# PiHat-Extended.net
KiCad netlist of a schematic drawn in EAGLE
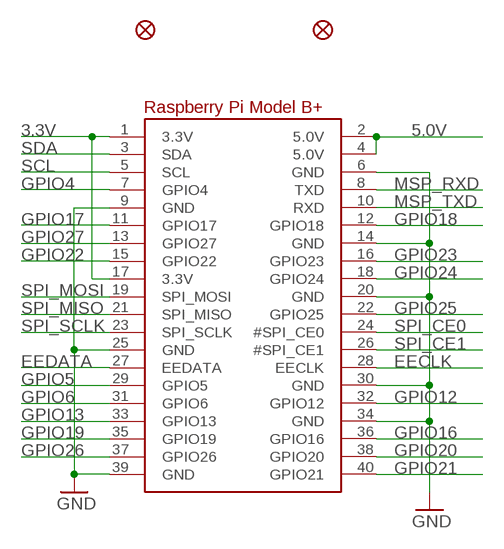
[diagram p0: schematic, sheet 1]
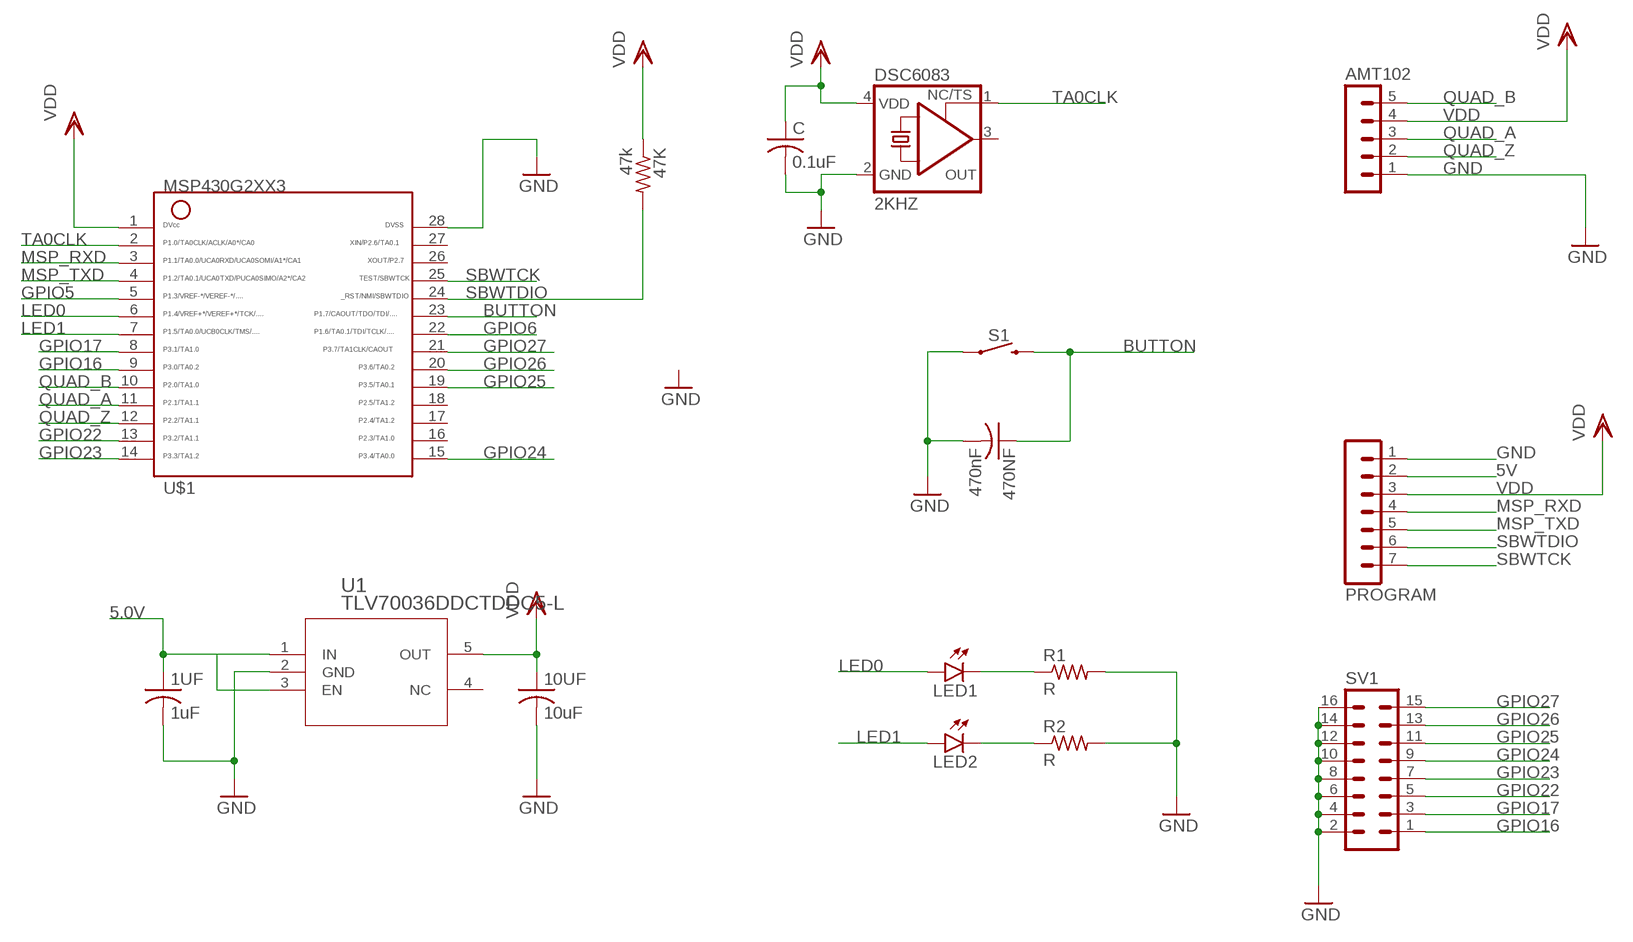
[diagram p1: schematic, sheet 2]
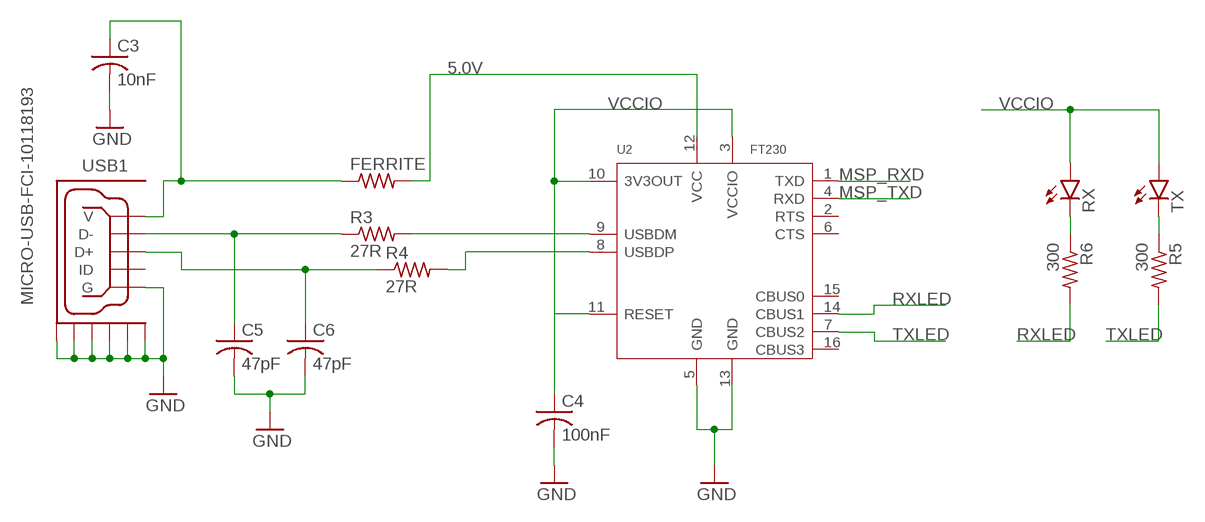
[diagram p2: schematic, sheet 3]
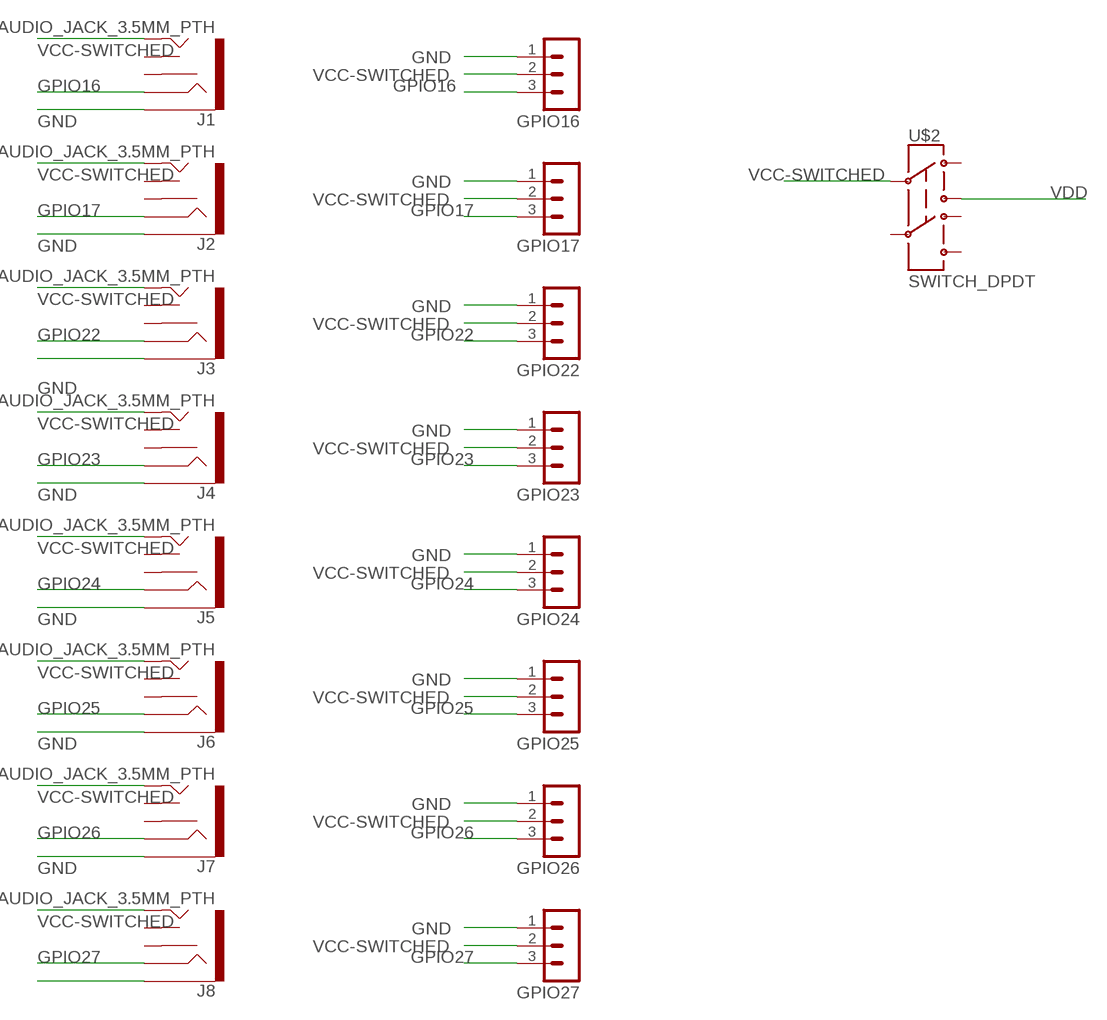
[diagram p3: schematic, sheet 4]

(export (version "E")
  (design (tool "Eeschema 10.0.6"))
  (components
    (comp (ref "GPIO16")
      (value "MA03-1")
      (footprint "eagle-import:MA03-1")
      (libsource (lib "eagle-import") (part "MA03-1"))
    )
    (comp (ref "GPIO17")
      (value "MA03-1")
      (footprint "eagle-import:MA03-1")
      (libsource (lib "eagle-import") (part "MA03-1"))
    )
    (comp (ref "GPIO22")
      (value "MA03-1")
      (footprint "eagle-import:MA03-1")
      (libsource (lib "eagle-import") (part "MA03-1"))
    )
    (comp (ref "GPIO23")
      (value "MA03-1")
      (footprint "eagle-import:MA03-1")
      (libsource (lib "eagle-import") (part "MA03-1"))
    )
    (comp (ref "GPIO24")
      (value "MA03-1")
      (footprint "eagle-import:MA03-1")
      (libsource (lib "eagle-import") (part "MA03-1"))
    )
    (comp (ref "GPIO25")
      (value "MA03-1")
      (footprint "eagle-import:MA03-1")
      (libsource (lib "eagle-import") (part "MA03-1"))
    )
    (comp (ref "GPIO26")
      (value "MA03-1")
      (footprint "eagle-import:MA03-1")
      (libsource (lib "eagle-import") (part "MA03-1"))
    )
    (comp (ref "GPIO27")
      (value "MA03-1")
      (footprint "eagle-import:MA03-1")
      (libsource (lib "eagle-import") (part "MA03-1"))
    )
    (comp (ref "J1")
      (value "AUDIO_JACK_3.5MM_PTH")
      (footprint "eagle-import:AUDIO-JACK")
      (libsource (lib "eagle-import") (part "AUDIO_JACK_3.5MM_PTH"))
    )
    (comp (ref "J2")
      (value "AUDIO_JACK_3.5MM_PTH")
      (footprint "eagle-import:AUDIO-JACK")
      (libsource (lib "eagle-import") (part "AUDIO_JACK_3.5MM_PTH"))
    )
    (comp (ref "J3")
      (value "AUDIO_JACK_3.5MM_PTH")
      (footprint "eagle-import:AUDIO-JACK")
      (libsource (lib "eagle-import") (part "AUDIO_JACK_3.5MM_PTH"))
    )
    (comp (ref "J4")
      (value "AUDIO_JACK_3.5MM_PTH")
      (footprint "eagle-import:AUDIO-JACK")
      (libsource (lib "eagle-import") (part "AUDIO_JACK_3.5MM_PTH"))
    )
    (comp (ref "J5")
      (value "AUDIO_JACK_3.5MM_PTH")
      (footprint "eagle-import:AUDIO-JACK")
      (libsource (lib "eagle-import") (part "AUDIO_JACK_3.5MM_PTH"))
    )
    (comp (ref "J6")
      (value "AUDIO_JACK_3.5MM_PTH")
      (footprint "eagle-import:AUDIO-JACK")
      (libsource (lib "eagle-import") (part "AUDIO_JACK_3.5MM_PTH"))
    )
    (comp (ref "J7")
      (value "AUDIO_JACK_3.5MM_PTH")
      (footprint "eagle-import:AUDIO-JACK")
      (libsource (lib "eagle-import") (part "AUDIO_JACK_3.5MM_PTH"))
    )
    (comp (ref "J8")
      (value "AUDIO_JACK_3.5MM_PTH")
      (footprint "eagle-import:AUDIO-JACK")
      (libsource (lib "eagle-import") (part "AUDIO_JACK_3.5MM_PTH"))
    )
    (comp (ref "U$2")
      (value "SWITCH_DPDT")
      (footprint "eagle-import:JS_DPDT_TH")
      (libsource (lib "eagle-import") (part "SWITCH_DPDT"))
    )
    (comp (ref "C3")
      (value "10nF")
      (footprint "eagle-import:C0603")
      (libsource (lib "eagle-import") (part "resistor_348_C-USC0603"))
    )
    (comp (ref "C4")
      (value "100nF")
      (footprint "eagle-import:C0603")
      (libsource (lib "eagle-import") (part "resistor_348_C-USC0603"))
    )
    (comp (ref "C5")
      (value "47pF")
      (footprint "eagle-import:C0603")
      (libsource (lib "eagle-import") (part "resistor_348_C-USC0603"))
    )
    (comp (ref "C6")
      (value "47pF")
      (footprint "eagle-import:C0603")
      (libsource (lib "eagle-import") (part "resistor_348_C-USC0603"))
    )
    (comp (ref "FERRITE")
      (value "R-US_R0805")
      (footprint "eagle-import:R0805")
      (libsource (lib "eagle-import") (part "R-US_R0805"))
    )
    (comp (ref "R3")
      (value "27R")
      (footprint "eagle-import:R0603")
      (libsource (lib "eagle-import") (part "resistor_348_R-US_R0603"))
    )
    (comp (ref "R4")
      (value "27R")
      (footprint "eagle-import:R0603")
      (libsource (lib "eagle-import") (part "resistor_348_R-US_R0603"))
    )
    (comp (ref "R5")
      (value "300")
      (footprint "eagle-import:R0603")
      (libsource (lib "eagle-import") (part "resistor_348_R-US_R0603"))
    )
    (comp (ref "R6")
      (value "300")
      (footprint "eagle-import:R0603")
      (libsource (lib "eagle-import") (part "resistor_348_R-US_R0603"))
    )
    (comp (ref "RX")
      (value "LEDCHIPLED_1206")
      (footprint "eagle-import:CHIPLED_1206")
      (libsource (lib "eagle-import") (part "LEDCHIPLED_1206"))
    )
    (comp (ref "TX")
      (value "LEDCHIPLED_1206")
      (footprint "eagle-import:CHIPLED_1206")
      (libsource (lib "eagle-import") (part "LEDCHIPLED_1206"))
    )
    (comp (ref "U2")
      (value "FT230")
      (footprint "eagle-import:SSOP16-0.635-5X4MM")
      (fields (field (name "MPN") "FT230XS-R"))
      (libsource (lib "eagle-import") (part "INTERFACE-FT230XS-R(SSOP16)"))
    )
    (comp (ref "USB1")
      (value "MICRO-USB-FCI-10118193")
      (footprint "eagle-import:FCI-10118193-0001LF")
      (libsource (lib "eagle-import") (part "MICRO-USB-FCI-10118193"))
    )
    (comp (ref "1UF")
      (value "1uF")
      (footprint "eagle-import:C0603")
      (libsource (lib "eagle-import") (part "C-USC0603"))
    )
    (comp (ref "10UF")
      (value "10uF")
      (footprint "eagle-import:C1206")
      (libsource (lib "eagle-import") (part "C-USC1206"))
    )
    (comp (ref "47K")
      (value "47k")
      (footprint "eagle-import:R0603")
      (libsource (lib "eagle-import") (part "R-US_R0603"))
    )
    (comp (ref "470NF")
      (value "470nF")
      (footprint "eagle-import:C0603")
      (libsource (lib "eagle-import") (part "C-USC0603"))
    )
    (comp (ref "AMT102")
      (value "MA05-1")
      (footprint "eagle-import:MA05-1")
      (libsource (lib "eagle-import") (part "MA05-1"))
    )
    (comp (ref "C")
      (value "0.1uF")
      (footprint "eagle-import:C0603")
      (libsource (lib "eagle-import") (part "C-USC0603"))
    )
    (comp (ref "DSC6083")
      (value "2KHZ")
      (footprint "eagle-import:3.2X2.5_KXO-V96")
      (libsource (lib "eagle-import") (part "KXO-PXO/XO-V96"))
    )
    (comp (ref "LED1")
      (value "LEDCHIPLED_1206")
      (footprint "eagle-import:CHIPLED_1206")
      (libsource (lib "eagle-import") (part "LEDCHIPLED_1206"))
    )
    (comp (ref "LED2")
      (value "LEDCHIPLED_1206")
      (footprint "eagle-import:CHIPLED_1206")
      (libsource (lib "eagle-import") (part "LEDCHIPLED_1206"))
    )
    (comp (ref "PROGRAM")
      (value "MA07-1")
      (footprint "eagle-import:MA07-1")
      (libsource (lib "eagle-import") (part "MA07-1"))
    )
    (comp (ref "R1")
      (value "R")
      (footprint "eagle-import:R0603")
      (libsource (lib "eagle-import") (part "R-US_R0603"))
    )
    (comp (ref "R2")
      (value "R")
      (footprint "eagle-import:R0603")
      (libsource (lib "eagle-import") (part "R-US_R0603"))
    )
    (comp (ref "S1")
      (value "MOMENTARY-SWITCH-SPST-PTH-6.0MM")
      (footprint "eagle-import:TACTILE_SWITCH_PTH_6.0MM")
      (libsource (lib "eagle-import") (part "MOMENTARY-SWITCH-SPST-PTH-6.0MM"))
    )
    (comp (ref "SV1")
      (value "MA08-2")
      (footprint "eagle-import:MA08-2")
      (libsource (lib "eagle-import") (part "MA08-2"))
    )
    (comp (ref "U$1")
      (value "MSP430")
      (footprint "eagle-import:PW28")
      (libsource (lib "eagle-import") (part "G2XX3---PW28"))
    )
    (comp (ref "U1")
      (value "TLV70036DDCTDDC5-L")
      (footprint "eagle-import:DDC5-L")
      (fields (field (name "MANUFACTURER_PART_NUMBER") "TLV70036DDCT"))
      (libsource (lib "eagle-import") (part "TLV70036DDCTDDC5-L"))
    )
    (comp (ref "FID2")
      (value "MICROBUILDER_FIDUCIAL\"\"")
      (footprint "eagle-import:MICROBUILDER_FIDUCIAL_1MM")
      (libsource (lib "eagle-import") (part "MICROBUILDER_FIDUCIAL{dblquote}{dblquote}"))
    )
    (comp (ref "FID3")
      (value "MICROBUILDER_FIDUCIAL\"\"")
      (footprint "eagle-import:MICROBUILDER_FIDUCIAL_1MM")
      (libsource (lib "eagle-import") (part "MICROBUILDER_FIDUCIAL{dblquote}{dblquote}"))
    )
    (comp (ref "RPI1")
      (value "MICROBUILDER_RASPBERRYPI_BPLUS_HATNOSLOTS")
      (footprint "eagle-import:MICROBUILDER_PI_HAT_NOSLOTS")
      (libsource (lib "eagle-import") (part "MICROBUILDER_RASPBERRYPI_BPLUS_HATNOSLOTS"))
    )
  )
  (nets
    (net (code "1") (name "3.3V") (class "Default")
      (node (ref "RPI1") (pin "1") (pinfunction "3.3V_1") (pintype "power_in"))
      (node (ref "RPI1") (pin "17") (pinfunction "3.3V_17") (pintype "power_in"))
    )
    (net (code "2") (name "5.0V") (class "Default")
      (node (ref "1UF") (pin "1") (pinfunction "1_1") (pintype "passive"))
      (node (ref "FERRITE") (pin "2") (pinfunction "2_2") (pintype "passive"))
      (node (ref "RPI1") (pin "2") (pinfunction "5.0V_2") (pintype "power_in"))
      (node (ref "RPI1") (pin "4") (pinfunction "5.0V_4") (pintype "power_in"))
      (node (ref "U1") (pin "1") (pinfunction "IN_1") (pintype "input"))
      (node (ref "U1") (pin "3") (pinfunction "EN_3") (pintype "passive"))
      (node (ref "U2") (pin "12") (pinfunction "VCC_12") (pintype "bidirectional"))
    )
    (net (code "3") (name "5V") (class "Default")
      (node (ref "PROGRAM") (pin "2") (pinfunction "2_2") (pintype "passive"))
    )
    (net (code "4") (name "BUTTON") (class "Default")
      (node (ref "470NF") (pin "1") (pinfunction "1_1") (pintype "passive"))
      (node (ref "S1") (pin "3") (pinfunction "2_3") (pintype "passive"))
      (node (ref "U$1") (pin "23") (pinfunction "23_23") (pintype "bidirectional"))
    )
    (net (code "5") (name "EECLK") (class "Default")
      (node (ref "RPI1") (pin "28") (pinfunction "EECLK_28") (pintype "power_in"))
    )
    (net (code "6") (name "EEDATA") (class "Default")
      (node (ref "RPI1") (pin "27") (pinfunction "EEDATA_27") (pintype "bidirectional"))
    )
    (net (code "7") (name "GND") (class "Default")
      (node (ref "10UF") (pin "2") (pinfunction "2_2") (pintype "passive"))
      (node (ref "1UF") (pin "2") (pinfunction "2_2") (pintype "passive"))
      (node (ref "470NF") (pin "2") (pinfunction "2_2") (pintype "passive"))
      (node (ref "AMT102") (pin "1") (pinfunction "1_1") (pintype "passive"))
      (node (ref "C") (pin "2") (pinfunction "2_2") (pintype "passive"))
      (node (ref "C3") (pin "2") (pinfunction "2_2") (pintype "passive"))
      (node (ref "C4") (pin "2") (pinfunction "2_2") (pintype "passive"))
      (node (ref "C5") (pin "2") (pinfunction "2_2") (pintype "passive"))
      (node (ref "C6") (pin "2") (pinfunction "2_2") (pintype "passive"))
      (node (ref "DSC6083") (pin "2") (pinfunction "GND_2") (pintype "power_in"))
      (node (ref "GPIO16") (pin "1") (pinfunction "1_1") (pintype "passive"))
      (node (ref "GPIO17") (pin "1") (pinfunction "1_1") (pintype "passive"))
      (node (ref "GPIO22") (pin "1") (pinfunction "1_1") (pintype "passive"))
      (node (ref "GPIO23") (pin "1") (pinfunction "1_1") (pintype "passive"))
      (node (ref "GPIO24") (pin "1") (pinfunction "1_1") (pintype "passive"))
      (node (ref "GPIO25") (pin "1") (pinfunction "1_1") (pintype "passive"))
      (node (ref "GPIO26") (pin "1") (pinfunction "1_1") (pintype "passive"))
      (node (ref "GPIO27") (pin "1") (pinfunction "1_1") (pintype "passive"))
      (node (ref "J1") (pin "SLEEVE") (pinfunction "SLEEVE_SLEEVE") (pintype "bidirectional"))
      (node (ref "J2") (pin "SLEEVE") (pinfunction "SLEEVE_SLEEVE") (pintype "bidirectional"))
      (node (ref "J3") (pin "SLEEVE") (pinfunction "SLEEVE_SLEEVE") (pintype "bidirectional"))
      (node (ref "J4") (pin "SLEEVE") (pinfunction "SLEEVE_SLEEVE") (pintype "bidirectional"))
      (node (ref "J5") (pin "SLEEVE") (pinfunction "SLEEVE_SLEEVE") (pintype "bidirectional"))
      (node (ref "J6") (pin "SLEEVE") (pinfunction "SLEEVE_SLEEVE") (pintype "bidirectional"))
      (node (ref "J7") (pin "SLEEVE") (pinfunction "SLEEVE_SLEEVE") (pintype "bidirectional"))
      (node (ref "J8") (pin "SLEEVE") (pinfunction "SLEEVE_SLEEVE") (pintype "bidirectional"))
      (node (ref "PROGRAM") (pin "1") (pinfunction "1_1") (pintype "passive"))
      (node (ref "R1") (pin "2") (pinfunction "2_2") (pintype "passive"))
      (node (ref "R2") (pin "2") (pinfunction "2_2") (pintype "passive"))
      (node (ref "RPI1") (pin "14") (pinfunction "GND_14") (pintype "power_in"))
      (node (ref "RPI1") (pin "20") (pinfunction "GND_20") (pintype "power_in"))
      (node (ref "RPI1") (pin "25") (pinfunction "GND_25") (pintype "power_in"))
      (node (ref "RPI1") (pin "30") (pinfunction "GND_30") (pintype "bidirectional"))
      (node (ref "RPI1") (pin "34") (pinfunction "GND_34") (pintype "bidirectional"))
      (node (ref "RPI1") (pin "39") (pinfunction "GND_39") (pintype "power_in"))
      (node (ref "RPI1") (pin "6") (pinfunction "GND_6") (pintype "power_in"))
      (node (ref "RPI1") (pin "9") (pinfunction "GND_9") (pintype "power_in"))
      (node (ref "S1") (pin "1") (pinfunction "1_1") (pintype "passive"))
      (node (ref "SV1") (pin "10") (pinfunction "10_10") (pintype "passive"))
      (node (ref "SV1") (pin "12") (pinfunction "12_12") (pintype "passive"))
      (node (ref "SV1") (pin "14") (pinfunction "14_14") (pintype "passive"))
      (node (ref "SV1") (pin "16") (pinfunction "16_16") (pintype "passive"))
      (node (ref "SV1") (pin "2") (pinfunction "2_2") (pintype "passive"))
      (node (ref "SV1") (pin "4") (pinfunction "4_4") (pintype "passive"))
      (node (ref "SV1") (pin "6") (pinfunction "6_6") (pintype "passive"))
      (node (ref "SV1") (pin "8") (pinfunction "8_8") (pintype "passive"))
      (node (ref "U$1") (pin "28") (pinfunction "28_28") (pintype "bidirectional"))
      (node (ref "U1") (pin "2") (pinfunction "GND_2") (pintype "power_in"))
      (node (ref "U2") (pin "13") (pinfunction "GND_13") (pintype "bidirectional"))
      (node (ref "U2") (pin "5") (pinfunction "GND_5") (pintype "bidirectional"))
      (node (ref "USB1") (pin "5") (pinfunction "G_5") (pintype "input"))
      (node (ref "USB1") (pin "G1") (pinfunction "GND1_G1") (pintype "power_in"))
      (node (ref "USB1") (pin "G2") (pinfunction "GND2_G2") (pintype "power_in"))
      (node (ref "USB1") (pin "G3") (pinfunction "GND3_G3") (pintype "power_in"))
      (node (ref "USB1") (pin "G4") (pinfunction "GND4_G4") (pintype "power_in"))
      (node (ref "USB1") (pin "G5") (pinfunction "GND5_G5") (pintype "power_in"))
      (node (ref "USB1") (pin "G6") (pinfunction "GND6_G6") (pintype "power_in"))
    )
    (net (code "8") (name "GPIO4") (class "Default")
      (node (ref "RPI1") (pin "7") (pinfunction "GPIO4_7") (pintype "bidirectional"))
    )
    (net (code "9") (name "GPIO5") (class "Default")
      (node (ref "RPI1") (pin "29") (pinfunction "GPIO5_29") (pintype "bidirectional"))
      (node (ref "U$1") (pin "5") (pinfunction "5_5") (pintype "bidirectional"))
    )
    (net (code "10") (name "GPIO6") (class "Default")
      (node (ref "RPI1") (pin "31") (pinfunction "GPIO6_31") (pintype "power_in"))
      (node (ref "U$1") (pin "22") (pinfunction "22_22") (pintype "bidirectional"))
    )
    (net (code "11") (name "GPIO12") (class "Default")
      (node (ref "RPI1") (pin "32") (pinfunction "GPIO12_32") (pintype "bidirectional"))
    )
    (net (code "12") (name "GPIO13") (class "Default")
      (node (ref "RPI1") (pin "33") (pinfunction "GPIO13_33") (pintype "bidirectional"))
    )
    (net (code "13") (name "GPIO16") (class "Default")
      (node (ref "GPIO16") (pin "3") (pinfunction "3_3") (pintype "passive"))
      (node (ref "J1") (pin "RING") (pinfunction "RING_RING") (pintype "bidirectional"))
      (node (ref "RPI1") (pin "36") (pinfunction "GPIO16_36") (pintype "power_in"))
      (node (ref "SV1") (pin "1") (pinfunction "1_1") (pintype "passive"))
      (node (ref "U$1") (pin "9") (pinfunction "9_9") (pintype "bidirectional"))
    )
    (net (code "14") (name "GPIO17") (class "Default")
      (node (ref "GPIO17") (pin "3") (pinfunction "3_3") (pintype "passive"))
      (node (ref "J2") (pin "RING") (pinfunction "RING_RING") (pintype "bidirectional"))
      (node (ref "RPI1") (pin "11") (pinfunction "GPIO17_11") (pintype "bidirectional"))
      (node (ref "SV1") (pin "3") (pinfunction "3_3") (pintype "passive"))
      (node (ref "U$1") (pin "8") (pinfunction "8_8") (pintype "bidirectional"))
    )
    (net (code "15") (name "GPIO18") (class "Default")
      (node (ref "RPI1") (pin "12") (pinfunction "GPIO18_12") (pintype "bidirectional"))
    )
    (net (code "16") (name "GPIO19") (class "Default")
      (node (ref "RPI1") (pin "35") (pinfunction "GPIO19_35") (pintype "bidirectional"))
    )
    (net (code "17") (name "GPIO20") (class "Default")
      (node (ref "RPI1") (pin "38") (pinfunction "GPIO20_38") (pintype "bidirectional"))
    )
    (net (code "18") (name "GPIO21") (class "Default")
      (node (ref "RPI1") (pin "40") (pinfunction "GPIO21_40") (pintype "bidirectional"))
    )
    (net (code "19") (name "GPIO22") (class "Default")
      (node (ref "GPIO22") (pin "3") (pinfunction "3_3") (pintype "passive"))
      (node (ref "J3") (pin "RING") (pinfunction "RING_RING") (pintype "bidirectional"))
      (node (ref "RPI1") (pin "15") (pinfunction "GPIO22_15") (pintype "bidirectional"))
      (node (ref "SV1") (pin "5") (pinfunction "5_5") (pintype "passive"))
      (node (ref "U$1") (pin "13") (pinfunction "13_13") (pintype "bidirectional"))
    )
    (net (code "20") (name "GPIO23") (class "Default")
      (node (ref "GPIO23") (pin "3") (pinfunction "3_3") (pintype "passive"))
      (node (ref "J4") (pin "RING") (pinfunction "RING_RING") (pintype "bidirectional"))
      (node (ref "RPI1") (pin "16") (pinfunction "GPIO23_16") (pintype "bidirectional"))
      (node (ref "SV1") (pin "7") (pinfunction "7_7") (pintype "passive"))
      (node (ref "U$1") (pin "14") (pinfunction "14_14") (pintype "bidirectional"))
    )
    (net (code "21") (name "GPIO24") (class "Default")
      (node (ref "GPIO24") (pin "3") (pinfunction "3_3") (pintype "passive"))
      (node (ref "J5") (pin "RING") (pinfunction "RING_RING") (pintype "bidirectional"))
      (node (ref "RPI1") (pin "18") (pinfunction "GPIO24_18") (pintype "bidirectional"))
      (node (ref "SV1") (pin "9") (pinfunction "9_9") (pintype "passive"))
      (node (ref "U$1") (pin "15") (pinfunction "15_15") (pintype "bidirectional"))
    )
    (net (code "22") (name "GPIO25") (class "Default")
      (node (ref "GPIO25") (pin "3") (pinfunction "3_3") (pintype "passive"))
      (node (ref "J6") (pin "RING") (pinfunction "RING_RING") (pintype "bidirectional"))
      (node (ref "RPI1") (pin "22") (pinfunction "GPIO25_22") (pintype "bidirectional"))
      (node (ref "SV1") (pin "11") (pinfunction "11_11") (pintype "passive"))
      (node (ref "U$1") (pin "19") (pinfunction "19_19") (pintype "bidirectional"))
    )
    (net (code "23") (name "GPIO26") (class "Default")
      (node (ref "GPIO26") (pin "3") (pinfunction "3_3") (pintype "passive"))
      (node (ref "J7") (pin "RING") (pinfunction "RING_RING") (pintype "bidirectional"))
      (node (ref "RPI1") (pin "37") (pinfunction "GPIO26_37") (pintype "bidirectional"))
      (node (ref "SV1") (pin "13") (pinfunction "13_13") (pintype "passive"))
      (node (ref "U$1") (pin "20") (pinfunction "20_20") (pintype "bidirectional"))
    )
    (net (code "24") (name "GPIO27") (class "Default")
      (node (ref "GPIO27") (pin "3") (pinfunction "3_3") (pintype "passive"))
      (node (ref "J8") (pin "RING") (pinfunction "RING_RING") (pintype "bidirectional"))
      (node (ref "RPI1") (pin "13") (pinfunction "GPIO27_13") (pintype "bidirectional"))
      (node (ref "SV1") (pin "15") (pinfunction "15_15") (pintype "passive"))
      (node (ref "U$1") (pin "21") (pinfunction "21_21") (pintype "bidirectional"))
    )
    (net (code "25") (name "LED0") (class "Default")
      (node (ref "LED1") (pin "A") (pinfunction "A_A") (pintype "passive"))
      (node (ref "U$1") (pin "6") (pinfunction "6_6") (pintype "bidirectional"))
    )
    (net (code "26") (name "LED1") (class "Default")
      (node (ref "LED2") (pin "A") (pinfunction "A_A") (pintype "passive"))
      (node (ref "U$1") (pin "7") (pinfunction "7_7") (pintype "bidirectional"))
    )
    (net (code "27") (name "MSP_RXD") (class "Default")
      (node (ref "PROGRAM") (pin "4") (pinfunction "4_4") (pintype "passive"))
      (node (ref "RPI1") (pin "8") (pinfunction "TXD_8") (pintype "output"))
      (node (ref "U$1") (pin "3") (pinfunction "3_3") (pintype "bidirectional"))
      (node (ref "U2") (pin "1") (pinfunction "TXD_1") (pintype "bidirectional"))
    )
    (net (code "28") (name "MSP_TXD") (class "Default")
      (node (ref "PROGRAM") (pin "5") (pinfunction "5_5") (pintype "passive"))
      (node (ref "RPI1") (pin "10") (pinfunction "RXD_10") (pintype "bidirectional"))
      (node (ref "U$1") (pin "4") (pinfunction "4_4") (pintype "bidirectional"))
      (node (ref "U2") (pin "4") (pinfunction "RXD_4") (pintype "bidirectional"))
    )
    (net (code "29") (name "Net-(LED1-PadC)") (class "Default")
      (node (ref "LED1") (pin "C") (pinfunction "C_C") (pintype "passive"))
      (node (ref "R1") (pin "1") (pinfunction "1_1") (pintype "passive"))
    )
    (net (code "30") (name "Net-(LED2-PadC)") (class "Default")
      (node (ref "LED2") (pin "C") (pinfunction "C_C") (pintype "passive"))
      (node (ref "R2") (pin "1") (pinfunction "1_1") (pintype "passive"))
    )
    (net (code "31") (name "Net-(R5-Pad1)") (class "Default")
      (node (ref "R5") (pin "1") (pinfunction "1_1") (pintype "passive"))
      (node (ref "TX") (pin "C") (pinfunction "C_C") (pintype "passive"))
    )
    (net (code "32") (name "Net-(R6-Pad1)") (class "Default")
      (node (ref "R6") (pin "1") (pinfunction "1_1") (pintype "passive"))
      (node (ref "RX") (pin "C") (pinfunction "C_C") (pintype "passive"))
    )
    (net (code "33") (name "Net-(U2-USBDM)") (class "Default")
      (node (ref "R3") (pin "2") (pinfunction "2_2") (pintype "passive"))
      (node (ref "U2") (pin "9") (pinfunction "USBDM_9") (pintype "bidirectional"))
    )
    (net (code "34") (name "Net-(U2-USBDP)") (class "Default")
      (node (ref "R4") (pin "2") (pinfunction "2_2") (pintype "passive"))
      (node (ref "U2") (pin "8") (pinfunction "USBDP_8") (pintype "bidirectional"))
    )
    (net (code "35") (name "Net-(USB1-D+)") (class "Default")
      (node (ref "C6") (pin "1") (pinfunction "1_1") (pintype "passive"))
      (node (ref "R4") (pin "1") (pinfunction "1_1") (pintype "passive"))
      (node (ref "USB1") (pin "3") (pinfunction "D+_3") (pintype "input"))
    )
    (net (code "36") (name "Net-(USB1-D-)") (class "Default")
      (node (ref "C5") (pin "1") (pinfunction "1_1") (pintype "passive"))
      (node (ref "R3") (pin "1") (pinfunction "1_1") (pintype "passive"))
      (node (ref "USB1") (pin "2") (pinfunction "D-_2") (pintype "input"))
    )
    (net (code "37") (name "Net-(USB1-V)") (class "Default")
      (node (ref "C3") (pin "1") (pinfunction "1_1") (pintype "passive"))
      (node (ref "FERRITE") (pin "1") (pinfunction "1_1") (pintype "passive"))
      (node (ref "USB1") (pin "1") (pinfunction "V_1") (pintype "input"))
    )
    (net (code "38") (name "QUAD_A") (class "Default")
      (node (ref "AMT102") (pin "3") (pinfunction "3_3") (pintype "passive"))
      (node (ref "U$1") (pin "11") (pinfunction "11_11") (pintype "bidirectional"))
    )
    (net (code "39") (name "QUAD_B") (class "Default")
      (node (ref "AMT102") (pin "5") (pinfunction "5_5") (pintype "passive"))
      (node (ref "U$1") (pin "10") (pinfunction "10_10") (pintype "bidirectional"))
    )
    (net (code "40") (name "QUAD_Z") (class "Default")
      (node (ref "AMT102") (pin "2") (pinfunction "2_2") (pintype "passive"))
      (node (ref "U$1") (pin "12") (pinfunction "12_12") (pintype "bidirectional"))
    )
    (net (code "41") (name "RXLED") (class "Default")
      (node (ref "R6") (pin "2") (pinfunction "2_2") (pintype "passive"))
      (node (ref "U2") (pin "14") (pinfunction "CBUS1_14") (pintype "bidirectional"))
    )
    (net (code "42") (name "SBWTCK") (class "Default")
      (node (ref "PROGRAM") (pin "7") (pinfunction "7_7") (pintype "passive"))
      (node (ref "U$1") (pin "25") (pinfunction "25_25") (pintype "bidirectional"))
    )
    (net (code "43") (name "SBWTDIO") (class "Default")
      (node (ref "47K") (pin "2") (pinfunction "2_2") (pintype "passive"))
      (node (ref "PROGRAM") (pin "6") (pinfunction "6_6") (pintype "passive"))
      (node (ref "U$1") (pin "24") (pinfunction "24_24") (pintype "bidirectional"))
    )
    (net (code "44") (name "SCL") (class "Default")
      (node (ref "RPI1") (pin "5") (pinfunction "SCL_5") (pintype "bidirectional"))
    )
    (net (code "45") (name "SDA") (class "Default")
      (node (ref "RPI1") (pin "3") (pinfunction "SDA_3") (pintype "bidirectional"))
    )
    (net (code "46") (name "SPI_CE0") (class "Default")
      (node (ref "RPI1") (pin "24") (pinfunction "#SPI_CE0_24") (pintype "bidirectional"))
    )
    (net (code "47") (name "SPI_CE1") (class "Default")
      (node (ref "RPI1") (pin "26") (pinfunction "#SPI_CE1_26") (pintype "bidirectional"))
    )
    (net (code "48") (name "SPI_MISO") (class "Default")
      (node (ref "RPI1") (pin "21") (pinfunction "SPI_MISO_21") (pintype "bidirectional"))
    )
    (net (code "49") (name "SPI_MOSI") (class "Default")
      (node (ref "RPI1") (pin "19") (pinfunction "SPI_MOSI_19") (pintype "bidirectional"))
    )
    (net (code "50") (name "SPI_SCLK") (class "Default")
      (node (ref "RPI1") (pin "23") (pinfunction "SPI_SCLK_23") (pintype "bidirectional"))
    )
    (net (code "51") (name "TA0CLK") (class "Default")
      (node (ref "DSC6083") (pin "1") (pinfunction "TS_1") (pintype "passive"))
      (node (ref "U$1") (pin "2") (pinfunction "2_2") (pintype "bidirectional"))
    )
    (net (code "52") (name "TXLED") (class "Default")
      (node (ref "R5") (pin "2") (pinfunction "2_2") (pintype "passive"))
      (node (ref "U2") (pin "7") (pinfunction "CBUS2_7") (pintype "bidirectional"))
    )
    (net (code "53") (name "VCC-SWITCHED") (class "Default")
      (node (ref "GPIO16") (pin "2") (pinfunction "2_2") (pintype "passive"))
      (node (ref "GPIO17") (pin "2") (pinfunction "2_2") (pintype "passive"))
      (node (ref "GPIO22") (pin "2") (pinfunction "2_2") (pintype "passive"))
      (node (ref "GPIO23") (pin "2") (pinfunction "2_2") (pintype "passive"))
      (node (ref "GPIO24") (pin "2") (pinfunction "2_2") (pintype "passive"))
      (node (ref "GPIO25") (pin "2") (pinfunction "2_2") (pintype "passive"))
      (node (ref "GPIO26") (pin "2") (pinfunction "2_2") (pintype "passive"))
      (node (ref "GPIO27") (pin "2") (pinfunction "2_2") (pintype "passive"))
      (node (ref "J1") (pin "TIP") (pinfunction "TIP_TIP") (pintype "bidirectional"))
      (node (ref "J2") (pin "TIP") (pinfunction "TIP_TIP") (pintype "bidirectional"))
      (node (ref "J3") (pin "TIP") (pinfunction "TIP_TIP") (pintype "bidirectional"))
      (node (ref "J4") (pin "TIP") (pinfunction "TIP_TIP") (pintype "bidirectional"))
      (node (ref "J5") (pin "TIP") (pinfunction "TIP_TIP") (pintype "bidirectional"))
      (node (ref "J6") (pin "TIP") (pinfunction "TIP_TIP") (pintype "bidirectional"))
      (node (ref "J7") (pin "TIP") (pinfunction "TIP_TIP") (pintype "bidirectional"))
      (node (ref "J8") (pin "TIP") (pinfunction "TIP_TIP") (pintype "bidirectional"))
      (node (ref "U$2") (pin "2") (pinfunction "2_2") (pintype "bidirectional"))
    )
    (net (code "54") (name "VCCIO") (class "Default")
      (node (ref "C4") (pin "1") (pinfunction "1_1") (pintype "passive"))
      (node (ref "RX") (pin "A") (pinfunction "A_A") (pintype "passive"))
      (node (ref "TX") (pin "A") (pinfunction "A_A") (pintype "passive"))
      (node (ref "U2") (pin "10") (pinfunction "3V3OUT_10") (pintype "bidirectional"))
      (node (ref "U2") (pin "11") (pinfunction "RESET_11") (pintype "bidirectional"))
      (node (ref "U2") (pin "3") (pinfunction "VCCIO_3") (pintype "bidirectional"))
    )
    (net (code "55") (name "VDD") (class "Default")
      (node (ref "10UF") (pin "1") (pinfunction "1_1") (pintype "passive"))
      (node (ref "47K") (pin "1") (pinfunction "1_1") (pintype "passive"))
      (node (ref "AMT102") (pin "4") (pinfunction "4_4") (pintype "passive"))
      (node (ref "C") (pin "1") (pinfunction "1_1") (pintype "passive"))
      (node (ref "DSC6083") (pin "4") (pinfunction "VDD_4") (pintype "power_in"))
      (node (ref "PROGRAM") (pin "3") (pinfunction "3_3") (pintype "passive"))
      (node (ref "U$1") (pin "1") (pinfunction "1_1") (pintype "bidirectional"))
      (node (ref "U$2") (pin "3") (pinfunction "3_3") (pintype "bidirectional"))
      (node (ref "U1") (pin "5") (pinfunction "OUT_5") (pintype "output"))
    )
    (net (code "56") (name "unconnected-(DSC6083-OUT-Pad3)") (class "Default")
      (node (ref "DSC6083") (pin "3") (pinfunction "OUT_3") (pintype "output"))
    )
    (net (code "57") (name "unconnected-(J1-PadRSH)") (class "Default")
      (node (ref "J1") (pin "RSH") (pinfunction "RSH_RSH") (pintype "bidirectional"))
    )
    (net (code "58") (name "unconnected-(J1-PadTSH)") (class "Default")
      (node (ref "J1") (pin "TSH") (pinfunction "TSH_TSH") (pintype "bidirectional"))
    )
    (net (code "59") (name "unconnected-(J2-PadRSH)") (class "Default")
      (node (ref "J2") (pin "RSH") (pinfunction "RSH_RSH") (pintype "bidirectional"))
    )
    (net (code "60") (name "unconnected-(J2-PadTSH)") (class "Default")
      (node (ref "J2") (pin "TSH") (pinfunction "TSH_TSH") (pintype "bidirectional"))
    )
    (net (code "61") (name "unconnected-(J3-PadRSH)") (class "Default")
      (node (ref "J3") (pin "RSH") (pinfunction "RSH_RSH") (pintype "bidirectional"))
    )
    (net (code "62") (name "unconnected-(J3-PadTSH)") (class "Default")
      (node (ref "J3") (pin "TSH") (pinfunction "TSH_TSH") (pintype "bidirectional"))
    )
    (net (code "63") (name "unconnected-(J4-PadRSH)") (class "Default")
      (node (ref "J4") (pin "RSH") (pinfunction "RSH_RSH") (pintype "bidirectional"))
    )
    (net (code "64") (name "unconnected-(J4-PadTSH)") (class "Default")
      (node (ref "J4") (pin "TSH") (pinfunction "TSH_TSH") (pintype "bidirectional"))
    )
    (net (code "65") (name "unconnected-(J5-PadRSH)") (class "Default")
      (node (ref "J5") (pin "RSH") (pinfunction "RSH_RSH") (pintype "bidirectional"))
    )
    (net (code "66") (name "unconnected-(J5-PadTSH)") (class "Default")
      (node (ref "J5") (pin "TSH") (pinfunction "TSH_TSH") (pintype "bidirectional"))
    )
    (net (code "67") (name "unconnected-(J6-PadRSH)") (class "Default")
      (node (ref "J6") (pin "RSH") (pinfunction "RSH_RSH") (pintype "bidirectional"))
    )
    (net (code "68") (name "unconnected-(J6-PadTSH)") (class "Default")
      (node (ref "J6") (pin "TSH") (pinfunction "TSH_TSH") (pintype "bidirectional"))
    )
    (net (code "69") (name "unconnected-(J7-PadRSH)") (class "Default")
      (node (ref "J7") (pin "RSH") (pinfunction "RSH_RSH") (pintype "bidirectional"))
    )
    (net (code "70") (name "unconnected-(J7-PadTSH)") (class "Default")
      (node (ref "J7") (pin "TSH") (pinfunction "TSH_TSH") (pintype "bidirectional"))
    )
    (net (code "71") (name "unconnected-(J8-PadRSH)") (class "Default")
      (node (ref "J8") (pin "RSH") (pinfunction "RSH_RSH") (pintype "bidirectional"))
    )
    (net (code "72") (name "unconnected-(J8-PadTSH)") (class "Default")
      (node (ref "J8") (pin "TSH") (pinfunction "TSH_TSH") (pintype "bidirectional"))
    )
    (net (code "73") (name "unconnected-(U$1-Pad16)") (class "Default")
      (node (ref "U$1") (pin "16") (pinfunction "16_16") (pintype "bidirectional"))
    )
    (net (code "74") (name "unconnected-(U$1-Pad17)") (class "Default")
      (node (ref "U$1") (pin "17") (pinfunction "17_17") (pintype "bidirectional"))
    )
    (net (code "75") (name "unconnected-(U$1-Pad18)") (class "Default")
      (node (ref "U$1") (pin "18") (pinfunction "18_18") (pintype "bidirectional"))
    )
    (net (code "76") (name "unconnected-(U$1-Pad26)") (class "Default")
      (node (ref "U$1") (pin "26") (pinfunction "26_26") (pintype "bidirectional"))
    )
    (net (code "77") (name "unconnected-(U$1-Pad27)") (class "Default")
      (node (ref "U$1") (pin "27") (pinfunction "27_27") (pintype "bidirectional"))
    )
    (net (code "78") (name "unconnected-(U$2-Pad1)") (class "Default")
      (node (ref "U$2") (pin "1") (pinfunction "1_1") (pintype "bidirectional"))
    )
    (net (code "79") (name "unconnected-(U$2-Pad4)") (class "Default")
      (node (ref "U$2") (pin "4") (pinfunction "4_4") (pintype "bidirectional"))
    )
    (net (code "80") (name "unconnected-(U$2-Pad5)") (class "Default")
      (node (ref "U$2") (pin "5") (pinfunction "5_5") (pintype "bidirectional"))
    )
    (net (code "81") (name "unconnected-(U$2-Pad6)") (class "Default")
      (node (ref "U$2") (pin "6") (pinfunction "6_6") (pintype "bidirectional"))
    )
    (net (code "82") (name "unconnected-(U1-NC-Pad4)") (class "Default")
      (node (ref "U1") (pin "4") (pinfunction "NC_4") (pintype "passive"))
    )
    (net (code "83") (name "unconnected-(U2-CBUS0-Pad15)") (class "Default")
      (node (ref "U2") (pin "15") (pinfunction "CBUS0_15") (pintype "bidirectional"))
    )
    (net (code "84") (name "unconnected-(U2-CBUS3-Pad16)") (class "Default")
      (node (ref "U2") (pin "16") (pinfunction "CBUS3_16") (pintype "bidirectional"))
    )
    (net (code "85") (name "unconnected-(U2-CTS-Pad6)") (class "Default")
      (node (ref "U2") (pin "6") (pinfunction "CTS_6") (pintype "bidirectional"))
    )
    (net (code "86") (name "unconnected-(U2-RTS-Pad2)") (class "Default")
      (node (ref "U2") (pin "2") (pinfunction "RTS_2") (pintype "bidirectional"))
    )
    (net (code "87") (name "unconnected-(USB1-ID-Pad4)") (class "Default")
      (node (ref "USB1") (pin "4") (pinfunction "ID_4") (pintype "input"))
    )
  )
)
